# Audio_Input_Line_In.net
KiCad netlist of a schematic drawn in Altium Designer
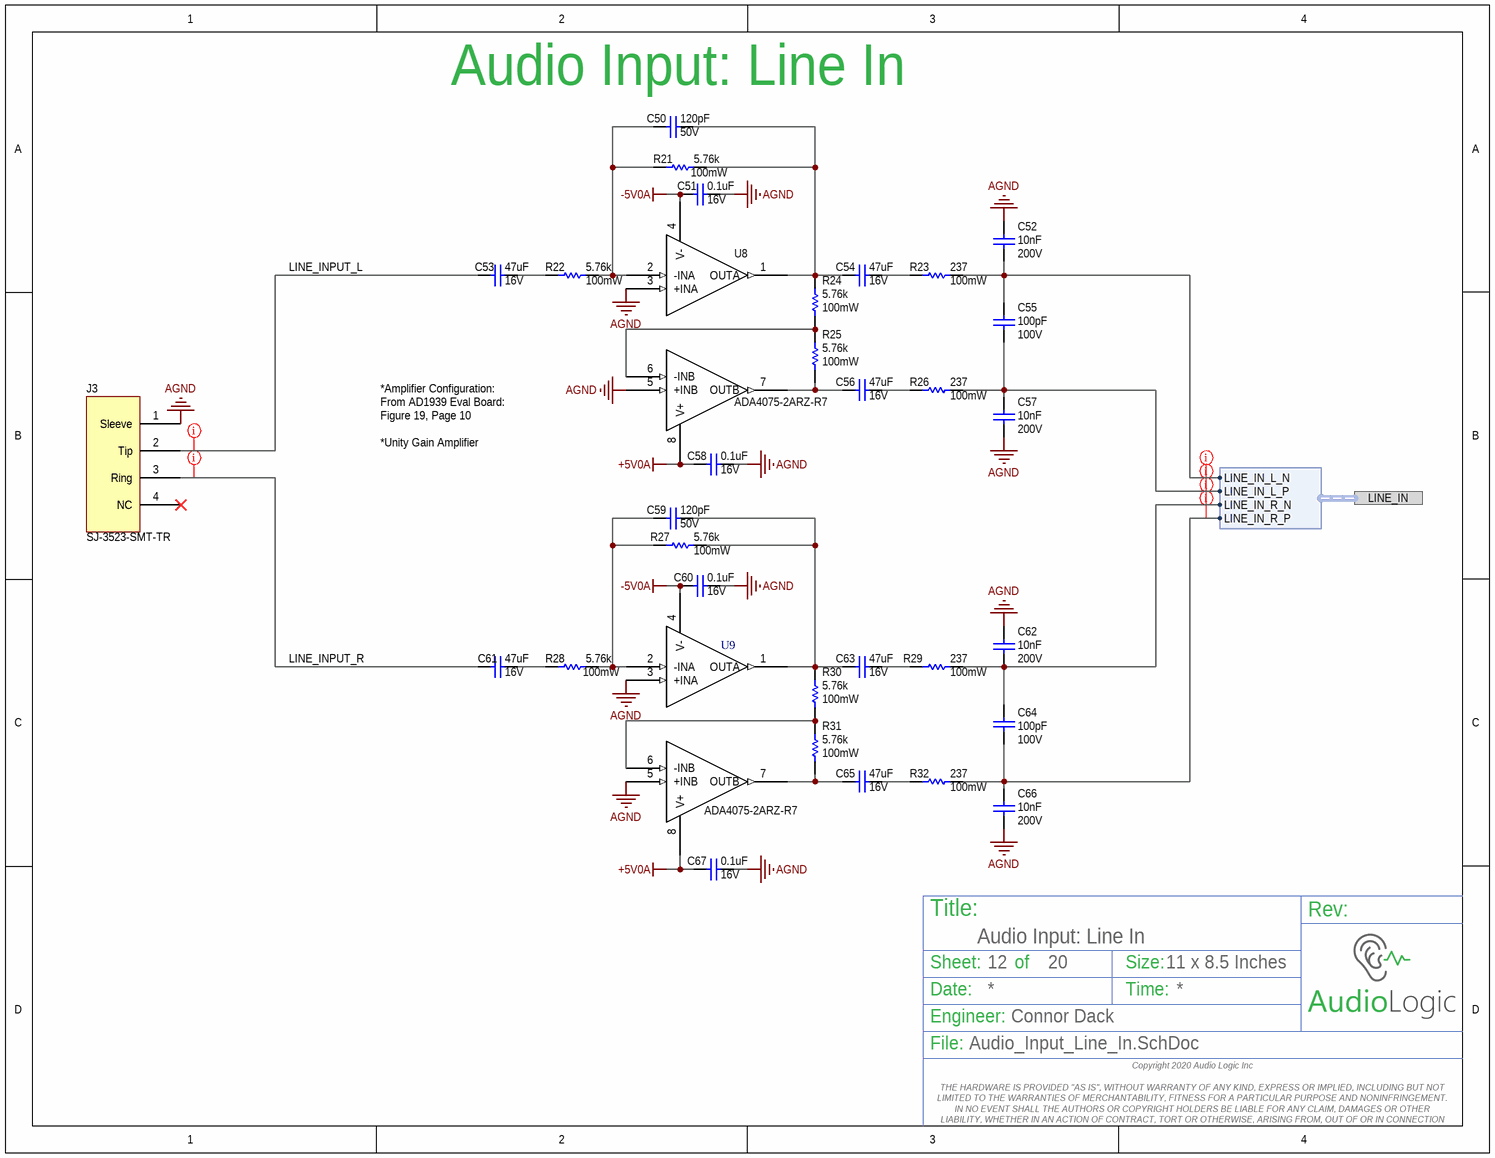
[diagram p0: Audio_Input_Line_In.SchDoc]

(export (version "E")
  (design (tool "Eeschema 10.0.6"))
  (components
    (comp (ref "C50")
      (value "CL10C121JB8NCNC")
      (footprint "3-0603_L")
      (description "120pF 50V Ceramic Capacitor C0G, NP0 0603 (1608 Metric) 0.063\" L x 0.031\" W (1.60mm x 0.80mm)")
      (fields
        (field (name "MANUFACTURER") "Samsung Electro-Mechanics America, Inc.")
        (field (name "TOLERANCE") "±5%")
        (field (name "VOLTAGE - RATED") "50V")
        (field (name "CAPACITANCE") "120pF")
      )
      (libsource (lib "Schematic_Components") (part "CL10C121JB8NCNC"))
    )
    (comp (ref "C51")
      (value "CL10F104ZO8NNNC")
      (footprint "3-0603_L")
      (description "CAP CER 0.1UF 16V Y5V 0603")
      (fields
        (field (name "MANUFACTURER") "Samsung")
        (field (name "TOLERANCE") "80%")
        (field (name "VOLTAGE RATING") "16V")
        (field (name "CAPACITANCE") "0.1uF")
      )
      (libsource (lib "Schematic_Components_CD") (part "CL10F104ZO8NNNC"))
    )
    (comp (ref "C52")
      (value "~")
      (footprint "3-0603_L")
      (description "CAP CER 10000PF 200V X7R 0603")
      (fields
        (field (name "MANUFACTURER") "KEMET")
        (field (name "MANUFACTURER PART NUMBER") "C0603C103J2RACTU")
        (field (name "VOLTAGE RATING") "200V")
        (field (name "CAPACITANCE") "10nF")
      )
      (libsource (lib "Miscellaneous Devices") (part "C0603C103J2RACTU"))
    )
    (comp (ref "C53")
      (value "CL32A476KOJNNNE")
      (footprint "C1210X25_L")
      (description "CAP CER 47UF 16V X5R 1210")
      (fields
        (field (name "MANUFACTURER") "Samsung")
        (field (name "TOLERANCE") "10%")
        (field (name "VOLTAGE RATING") "16V")
        (field (name "CAPACITANCE") "47uF")
      )
      (libsource (lib "Schematic_Components_CD") (part "CL32A476KOJNNNE"))
    )
    (comp (ref "C54")
      (value "CL32A476KOJNNNE")
      (footprint "C1210X25_L")
      (description "CAP CER 47UF 16V X5R 1210")
      (fields
        (field (name "MANUFACTURER") "Samsung")
        (field (name "TOLERANCE") "10%")
        (field (name "VOLTAGE RATING") "16V")
        (field (name "CAPACITANCE") "47uF")
      )
      (libsource (lib "Schematic_Components_CD") (part "CL32A476KOJNNNE"))
    )
    (comp (ref "C55")
      (value "C1608C0G2A101J")
      (footprint "3-0603_L")
      (description "CAP CER 100PF 100V 5% NP0 0603")
      (fields
        (field (name "MANUFACTURER") "TDK Corporation")
        (field (name "VOLTAGE - RATED") "100V")
        (field (name "TOLERANCE") "±5%")
        (field (name "CAPACITANCE") "100pF")
      )
      (libsource (lib "Schematic_Components") (part "C1608C0G2A101J"))
    )
    (comp (ref "C56")
      (value "CL32A476KOJNNNE")
      (footprint "C1210X25_L")
      (description "CAP CER 47UF 16V X5R 1210")
      (fields
        (field (name "MANUFACTURER") "Samsung")
        (field (name "TOLERANCE") "10%")
        (field (name "VOLTAGE RATING") "16V")
        (field (name "CAPACITANCE") "47uF")
      )
      (libsource (lib "Schematic_Components_CD") (part "CL32A476KOJNNNE"))
    )
    (comp (ref "C57")
      (value "~")
      (footprint "3-0603_L")
      (description "CAP CER 10000PF 200V X7R 0603")
      (fields
        (field (name "MANUFACTURER") "KEMET")
        (field (name "MANUFACTURER PART NUMBER") "C0603C103J2RACTU")
        (field (name "VOLTAGE RATING") "200V")
        (field (name "CAPACITANCE") "10nF")
      )
      (libsource (lib "Miscellaneous Devices") (part "C0603C103J2RACTU"))
    )
    (comp (ref "C58")
      (value "CL10F104ZO8NNNC")
      (footprint "3-0603_L")
      (description "CAP CER 0.1UF 16V Y5V 0603")
      (fields
        (field (name "MANUFACTURER") "Samsung")
        (field (name "TOLERANCE") "80%")
        (field (name "VOLTAGE RATING") "16V")
        (field (name "CAPACITANCE") "0.1uF")
      )
      (libsource (lib "Schematic_Components_CD") (part "CL10F104ZO8NNNC"))
    )
    (comp (ref "C59")
      (value "CL10C121JB8NCNC")
      (footprint "3-0603_L")
      (description "120pF 50V Ceramic Capacitor C0G, NP0 0603 (1608 Metric) 0.063\" L x 0.031\" W (1.60mm x 0.80mm)")
      (fields
        (field (name "MANUFACTURER") "Samsung Electro-Mechanics America, Inc.")
        (field (name "TOLERANCE") "±5%")
        (field (name "VOLTAGE - RATED") "50V")
        (field (name "CAPACITANCE") "120pF")
      )
      (libsource (lib "Schematic_Components") (part "CL10C121JB8NCNC"))
    )
    (comp (ref "C60")
      (value "CL10F104ZO8NNNC")
      (footprint "3-0603_L")
      (description "CAP CER 0.1UF 16V Y5V 0603")
      (fields
        (field (name "MANUFACTURER") "Samsung")
        (field (name "TOLERANCE") "80%")
        (field (name "VOLTAGE RATING") "16V")
        (field (name "CAPACITANCE") "0.1uF")
      )
      (libsource (lib "Schematic_Components_CD") (part "CL10F104ZO8NNNC"))
    )
    (comp (ref "C61")
      (value "CL32A476KOJNNNE")
      (footprint "C1210X25_L")
      (description "CAP CER 47UF 16V X5R 1210")
      (fields
        (field (name "MANUFACTURER") "Samsung")
        (field (name "TOLERANCE") "10%")
        (field (name "VOLTAGE RATING") "16V")
        (field (name "CAPACITANCE") "47uF")
      )
      (libsource (lib "Schematic_Components_CD") (part "CL32A476KOJNNNE"))
    )
    (comp (ref "C62")
      (value "~")
      (footprint "3-0603_L")
      (description "CAP CER 10000PF 200V X7R 0603")
      (fields
        (field (name "MANUFACTURER") "KEMET")
        (field (name "MANUFACTURER PART NUMBER") "C0603C103J2RACTU")
        (field (name "VOLTAGE RATING") "200V")
        (field (name "CAPACITANCE") "10nF")
      )
      (libsource (lib "Miscellaneous Devices") (part "C0603C103J2RACTU"))
    )
    (comp (ref "C63")
      (value "CL32A476KOJNNNE")
      (footprint "C1210X25_L")
      (description "CAP CER 47UF 16V X5R 1210")
      (fields
        (field (name "MANUFACTURER") "Samsung")
        (field (name "TOLERANCE") "10%")
        (field (name "VOLTAGE RATING") "16V")
        (field (name "CAPACITANCE") "47uF")
      )
      (libsource (lib "Schematic_Components_CD") (part "CL32A476KOJNNNE"))
    )
    (comp (ref "C64")
      (value "C1608C0G2A101J")
      (footprint "3-0603_L")
      (description "CAP CER 100PF 100V 5% NP0 0603")
      (fields
        (field (name "MANUFACTURER") "TDK Corporation")
        (field (name "VOLTAGE - RATED") "100V")
        (field (name "TOLERANCE") "±5%")
        (field (name "CAPACITANCE") "100pF")
      )
      (libsource (lib "Schematic_Components") (part "C1608C0G2A101J"))
    )
    (comp (ref "C65")
      (value "CL32A476KOJNNNE")
      (footprint "C1210X25_L")
      (description "CAP CER 47UF 16V X5R 1210")
      (fields
        (field (name "MANUFACTURER") "Samsung")
        (field (name "TOLERANCE") "10%")
        (field (name "VOLTAGE RATING") "16V")
        (field (name "CAPACITANCE") "47uF")
      )
      (libsource (lib "Schematic_Components_CD") (part "CL32A476KOJNNNE"))
    )
    (comp (ref "C66")
      (value "~")
      (footprint "3-0603_L")
      (description "CAP CER 10000PF 200V X7R 0603")
      (fields
        (field (name "MANUFACTURER") "KEMET")
        (field (name "MANUFACTURER PART NUMBER") "C0603C103J2RACTU")
        (field (name "VOLTAGE RATING") "200V")
        (field (name "CAPACITANCE") "10nF")
      )
      (libsource (lib "Miscellaneous Devices") (part "C0603C103J2RACTU"))
    )
    (comp (ref "C67")
      (value "CL10F104ZO8NNNC")
      (footprint "3-0603_L")
      (description "CAP CER 0.1UF 16V Y5V 0603")
      (fields
        (field (name "MANUFACTURER") "Samsung")
        (field (name "TOLERANCE") "80%")
        (field (name "VOLTAGE RATING") "16V")
        (field (name "CAPACITANCE") "0.1uF")
      )
      (libsource (lib "Schematic_Components_CD") (part "CL10F104ZO8NNNC"))
    )
    (comp (ref "J3")
      (value "SJ-3523-SMT-TR")
      (footprint "SJ-3523-SMT-TR")
      (description "3.50mm (0.141\", 1/8\", Mini Plug) - Headphone Phone Jack Stereo Connector Solder")
      (fields
        (field (name "MANUFACTURER") "CUI Inc.")
        (field (name "MANUFACTURER PART NUMBER") "SJ-3523-SMT-TR")
        (field (name "PUBLISHER") "Altium Limited")
      )
      (libsource (lib "NIH_DE0_Nano_Daughter_Card_Library") (part "SJ-3523-SMT-TR"))
    )
    (comp (ref "R21")
      (value "ERJ-3EKF5761V")
      (footprint "3-0603_R_L")
      (description "RES SMD 5.76K OHM 1% 1/10W 0603")
      (fields
        (field (name "MANUFACTURER") "Panasonic Electronic Components")
        (field (name "TOLERANCE") "±1%")
        (field (name "POWER (WATTS)") "100mW")
        (field (name "RESISTANCE (OHMS)") "5.76k")
      )
      (libsource (lib "Schematic_Components") (part "ERJ-3EKF5761V"))
    )
    (comp (ref "R22")
      (value "ERJ-3EKF5761V")
      (footprint "3-0603_R_L")
      (description "RES SMD 5.76K OHM 1% 1/10W 0603")
      (fields
        (field (name "MANUFACTURER") "Panasonic Electronic Components")
        (field (name "TOLERANCE") "±1%")
        (field (name "POWER (WATTS)") "100mW")
        (field (name "RESISTANCE (OHMS)") "5.76k")
      )
      (libsource (lib "Schematic_Components") (part "ERJ-3EKF5761V"))
    )
    (comp (ref "R23")
      (value "ERJ-3EKF2370V")
      (footprint "3-0603_R_L")
      (description "RES SMD 237 OHM 1% 1/10W 0603")
      (fields
        (field (name "MANUFACTURER") "Panasonic Electronic Components")
        (field (name "TOLERANCE") "±1%")
        (field (name "POWER (WATTS)") "100mW")
        (field (name "RESISTANCE (OHMS)") "237")
      )
      (libsource (lib "Schematic_Components") (part "ERJ-3EKF2370V"))
    )
    (comp (ref "R24")
      (value "ERJ-3EKF5761V")
      (footprint "3-0603_R_L")
      (description "RES SMD 5.76K OHM 1% 1/10W 0603")
      (fields
        (field (name "MANUFACTURER") "Panasonic Electronic Components")
        (field (name "TOLERANCE") "±1%")
        (field (name "POWER (WATTS)") "100mW")
        (field (name "RESISTANCE (OHMS)") "5.76k")
      )
      (libsource (lib "Schematic_Components") (part "ERJ-3EKF5761V"))
    )
    (comp (ref "R25")
      (value "ERJ-3EKF5761V")
      (footprint "3-0603_R_L")
      (description "RES SMD 5.76K OHM 1% 1/10W 0603")
      (fields
        (field (name "MANUFACTURER") "Panasonic Electronic Components")
        (field (name "TOLERANCE") "±1%")
        (field (name "POWER (WATTS)") "100mW")
        (field (name "RESISTANCE (OHMS)") "5.76k")
      )
      (libsource (lib "Schematic_Components") (part "ERJ-3EKF5761V"))
    )
    (comp (ref "R26")
      (value "ERJ-3EKF2370V")
      (footprint "3-0603_R_L")
      (description "RES SMD 237 OHM 1% 1/10W 0603")
      (fields
        (field (name "MANUFACTURER") "Panasonic Electronic Components")
        (field (name "TOLERANCE") "±1%")
        (field (name "POWER (WATTS)") "100mW")
        (field (name "RESISTANCE (OHMS)") "237")
      )
      (libsource (lib "Schematic_Components") (part "ERJ-3EKF2370V"))
    )
    (comp (ref "R27")
      (value "ERJ-3EKF5761V")
      (footprint "3-0603_R_L")
      (description "RES SMD 5.76K OHM 1% 1/10W 0603")
      (fields
        (field (name "MANUFACTURER") "Panasonic Electronic Components")
        (field (name "TOLERANCE") "±1%")
        (field (name "POWER (WATTS)") "100mW")
        (field (name "RESISTANCE (OHMS)") "5.76k")
      )
      (libsource (lib "Schematic_Components") (part "ERJ-3EKF5761V"))
    )
    (comp (ref "R28")
      (value "ERJ-3EKF5761V")
      (footprint "3-0603_R_L")
      (description "RES SMD 5.76K OHM 1% 1/10W 0603")
      (fields
        (field (name "MANUFACTURER") "Panasonic Electronic Components")
        (field (name "TOLERANCE") "±1%")
        (field (name "POWER (WATTS)") "100mW")
        (field (name "RESISTANCE (OHMS)") "5.76k")
      )
      (libsource (lib "Schematic_Components") (part "ERJ-3EKF5761V"))
    )
    (comp (ref "R29")
      (value "ERJ-3EKF2370V")
      (footprint "3-0603_R_L")
      (description "RES SMD 237 OHM 1% 1/10W 0603")
      (fields
        (field (name "MANUFACTURER") "Panasonic Electronic Components")
        (field (name "TOLERANCE") "±1%")
        (field (name "POWER (WATTS)") "100mW")
        (field (name "RESISTANCE (OHMS)") "237")
      )
      (libsource (lib "Schematic_Components") (part "ERJ-3EKF2370V"))
    )
    (comp (ref "R30")
      (value "ERJ-3EKF5761V")
      (footprint "3-0603_R_L")
      (description "RES SMD 5.76K OHM 1% 1/10W 0603")
      (fields
        (field (name "MANUFACTURER") "Panasonic Electronic Components")
        (field (name "TOLERANCE") "±1%")
        (field (name "POWER (WATTS)") "100mW")
        (field (name "RESISTANCE (OHMS)") "5.76k")
      )
      (libsource (lib "Schematic_Components") (part "ERJ-3EKF5761V"))
    )
    (comp (ref "R31")
      (value "ERJ-3EKF5761V")
      (footprint "3-0603_R_L")
      (description "RES SMD 5.76K OHM 1% 1/10W 0603")
      (fields
        (field (name "MANUFACTURER") "Panasonic Electronic Components")
        (field (name "TOLERANCE") "±1%")
        (field (name "POWER (WATTS)") "100mW")
        (field (name "RESISTANCE (OHMS)") "5.76k")
      )
      (libsource (lib "Schematic_Components") (part "ERJ-3EKF5761V"))
    )
    (comp (ref "R32")
      (value "ERJ-3EKF2370V")
      (footprint "3-0603_R_L")
      (description "RES SMD 237 OHM 1% 1/10W 0603")
      (fields
        (field (name "MANUFACTURER") "Panasonic Electronic Components")
        (field (name "TOLERANCE") "±1%")
        (field (name "POWER (WATTS)") "100mW")
        (field (name "RESISTANCE (OHMS)") "237")
      )
      (libsource (lib "Schematic_Components") (part "ERJ-3EKF2370V"))
    )
    (comp (ref "U8")
      (value "ADA4075-2ARZ-R7")
      (footprint "SOIC127P600X175-8L")
      (description "IC OPAMP GP 6.5MHZ 8SOIC")
      (fields
        (field (name "MANUFACTURER") "Analog Devices Inc.")
        (field (name "MANUFACTURER PART NUMBER") "ADA4075-2ARZ-R7")
      )
      (libsource (lib "Schematic_Components_CD") (part "ADA4075-2ARZ-R7"))
    )
    (comp (ref "U9")
      (value "ADA4075-2ARZ-R7")
      (footprint "SOIC127P600X175-8L")
      (description "IC OPAMP GP 6.5MHZ 8SOIC")
      (fields
        (field (name "MANUFACTURER") "Analog Devices Inc.")
        (field (name "MANUFACTURER PART NUMBER") "ADA4075-2ARZ-R7")
      )
      (libsource (lib "Schematic_Components_CD") (part "ADA4075-2ARZ-R7"))
    )
  )
  (nets
    (net (code "2") (name "+5V0A") (class "Default")
      (node (ref "C58") (pin "2") (pinfunction "2_2") (pintype "passive"))
      (node (ref "C67") (pin "2") (pinfunction "2_2") (pintype "passive"))
      (node (ref "U8") (pin "8") (pinfunction "V+_8") (pintype "passive"))
      (node (ref "U9") (pin "8") (pinfunction "V+_8") (pintype "passive"))
    )
    (net (code "3") (name "-5V0A") (class "Default")
      (node (ref "C51") (pin "2") (pinfunction "2_2") (pintype "passive"))
      (node (ref "C60") (pin "2") (pinfunction "2_2") (pintype "passive"))
      (node (ref "U8") (pin "4") (pinfunction "V-_4") (pintype "passive"))
      (node (ref "U9") (pin "4") (pinfunction "V-_4") (pintype "passive"))
    )
    (net (code "4") (name "/LINE_INPUT_L") (class "Default")
      (node (ref "C53") (pin "1") (pinfunction "1_1") (pintype "passive"))
      (node (ref "J3") (pin "2") (pinfunction "Tip_2") (pintype "passive"))
    )
    (net (code "5") (name "/LINE_INPUT_R") (class "Default")
      (node (ref "C61") (pin "1") (pinfunction "1_1") (pintype "passive"))
      (node (ref "J3") (pin "3") (pinfunction "Ring_3") (pintype "passive"))
    )
    (net (code "7") (name "AGND") (class "Default")
      (node (ref "C51") (pin "1") (pinfunction "1_1") (pintype "passive"))
      (node (ref "C52") (pin "2") (pinfunction "2_2") (pintype "passive"))
      (node (ref "C57") (pin "1") (pinfunction "1_1") (pintype "passive"))
      (node (ref "C58") (pin "1") (pinfunction "1_1") (pintype "passive"))
      (node (ref "C60") (pin "1") (pinfunction "1_1") (pintype "passive"))
      (node (ref "C62") (pin "2") (pinfunction "2_2") (pintype "passive"))
      (node (ref "C66") (pin "1") (pinfunction "1_1") (pintype "passive"))
      (node (ref "C67") (pin "1") (pinfunction "1_1") (pintype "passive"))
      (node (ref "J3") (pin "1") (pinfunction "Sleeve_1") (pintype "passive"))
      (node (ref "U8") (pin "3") (pinfunction "+INA_3") (pintype "input"))
      (node (ref "U8") (pin "5") (pinfunction "+INB_5") (pintype "input"))
      (node (ref "U9") (pin "3") (pinfunction "+INA_3") (pintype "input"))
      (node (ref "U9") (pin "5") (pinfunction "+INB_5") (pintype "input"))
    )
    (net (code "8") (name "Net-(C52-Pad1)") (class "Default")
      (node (ref "C52") (pin "1") (pinfunction "1_1") (pintype "passive"))
      (node (ref "C55") (pin "2") (pinfunction "2_2") (pintype "passive"))
      (node (ref "R23") (pin "2") (pinfunction "2_2") (pintype "passive"))
    )
    (net (code "9") (name "Net-(C53-Pad2)") (class "Default")
      (node (ref "C53") (pin "2") (pinfunction "2_2") (pintype "passive"))
      (node (ref "R22") (pin "1") (pinfunction "1_1") (pintype "passive"))
    )
    (net (code "10") (name "Net-(C54-Pad2)") (class "Default")
      (node (ref "C54") (pin "2") (pinfunction "2_2") (pintype "passive"))
      (node (ref "R23") (pin "1") (pinfunction "1_1") (pintype "passive"))
    )
    (net (code "11") (name "Net-(C55-Pad1)") (class "Default")
      (node (ref "C55") (pin "1") (pinfunction "1_1") (pintype "passive"))
      (node (ref "C57") (pin "2") (pinfunction "2_2") (pintype "passive"))
      (node (ref "R26") (pin "2") (pinfunction "2_2") (pintype "passive"))
    )
    (net (code "12") (name "Net-(C56-Pad2)") (class "Default")
      (node (ref "C56") (pin "2") (pinfunction "2_2") (pintype "passive"))
      (node (ref "R26") (pin "1") (pinfunction "1_1") (pintype "passive"))
    )
    (net (code "13") (name "Net-(C61-Pad2)") (class "Default")
      (node (ref "C61") (pin "2") (pinfunction "2_2") (pintype "passive"))
      (node (ref "R28") (pin "1") (pinfunction "1_1") (pintype "passive"))
    )
    (net (code "14") (name "Net-(C62-Pad1)") (class "Default")
      (node (ref "C62") (pin "1") (pinfunction "1_1") (pintype "passive"))
      (node (ref "C64") (pin "2") (pinfunction "2_2") (pintype "passive"))
      (node (ref "R29") (pin "2") (pinfunction "2_2") (pintype "passive"))
    )
    (net (code "15") (name "Net-(C63-Pad2)") (class "Default")
      (node (ref "C63") (pin "2") (pinfunction "2_2") (pintype "passive"))
      (node (ref "R29") (pin "1") (pinfunction "1_1") (pintype "passive"))
    )
    (net (code "16") (name "Net-(C64-Pad1)") (class "Default")
      (node (ref "C64") (pin "1") (pinfunction "1_1") (pintype "passive"))
      (node (ref "C66") (pin "2") (pinfunction "2_2") (pintype "passive"))
      (node (ref "R32") (pin "2") (pinfunction "2_2") (pintype "passive"))
    )
    (net (code "17") (name "Net-(C65-Pad2)") (class "Default")
      (node (ref "C65") (pin "2") (pinfunction "2_2") (pintype "passive"))
      (node (ref "R32") (pin "1") (pinfunction "1_1") (pintype "passive"))
    )
    (net (code "18") (name "Net-(U8--INA)") (class "Default")
      (node (ref "C50") (pin "1") (pinfunction "1_1") (pintype "passive"))
      (node (ref "R21") (pin "1") (pinfunction "1_1") (pintype "passive"))
      (node (ref "R22") (pin "2") (pinfunction "2_2") (pintype "passive"))
      (node (ref "U8") (pin "2") (pinfunction "-INA_2") (pintype "input"))
    )
    (net (code "19") (name "Net-(U8--INB)") (class "Default")
      (node (ref "R24") (pin "2") (pinfunction "2_2") (pintype "passive"))
      (node (ref "R25") (pin "2") (pinfunction "2_2") (pintype "passive"))
      (node (ref "U8") (pin "6") (pinfunction "-INB_6") (pintype "input"))
    )
    (net (code "20") (name "Net-(U8-OUTA)") (class "Default")
      (node (ref "C50") (pin "2") (pinfunction "2_2") (pintype "passive"))
      (node (ref "C54") (pin "1") (pinfunction "1_1") (pintype "passive"))
      (node (ref "R21") (pin "2") (pinfunction "2_2") (pintype "passive"))
      (node (ref "R24") (pin "1") (pinfunction "1_1") (pintype "passive"))
      (node (ref "U8") (pin "1") (pinfunction "OUTA_1") (pintype "output"))
    )
    (net (code "21") (name "Net-(U8-OUTB)") (class "Default")
      (node (ref "C56") (pin "1") (pinfunction "1_1") (pintype "passive"))
      (node (ref "R25") (pin "1") (pinfunction "1_1") (pintype "passive"))
      (node (ref "U8") (pin "7") (pinfunction "OUTB_7") (pintype "output"))
    )
    (net (code "22") (name "Net-(U9--INA)") (class "Default")
      (node (ref "C59") (pin "1") (pinfunction "1_1") (pintype "passive"))
      (node (ref "R27") (pin "1") (pinfunction "1_1") (pintype "passive"))
      (node (ref "R28") (pin "2") (pinfunction "2_2") (pintype "passive"))
      (node (ref "U9") (pin "2") (pinfunction "-INA_2") (pintype "input"))
    )
    (net (code "23") (name "Net-(U9--INB)") (class "Default")
      (node (ref "R30") (pin "1") (pinfunction "1_1") (pintype "passive"))
      (node (ref "R31") (pin "2") (pinfunction "2_2") (pintype "passive"))
      (node (ref "U9") (pin "6") (pinfunction "-INB_6") (pintype "input"))
    )
    (net (code "24") (name "Net-(U9-OUTA)") (class "Default")
      (node (ref "C59") (pin "2") (pinfunction "2_2") (pintype "passive"))
      (node (ref "C63") (pin "1") (pinfunction "1_1") (pintype "passive"))
      (node (ref "R27") (pin "2") (pinfunction "2_2") (pintype "passive"))
      (node (ref "R30") (pin "2") (pinfunction "2_2") (pintype "passive"))
      (node (ref "U9") (pin "1") (pinfunction "OUTA_1") (pintype "output"))
    )
    (net (code "25") (name "Net-(U9-OUTB)") (class "Default")
      (node (ref "C65") (pin "1") (pinfunction "1_1") (pintype "passive"))
      (node (ref "R31") (pin "1") (pinfunction "1_1") (pintype "passive"))
      (node (ref "U9") (pin "7") (pinfunction "OUTB_7") (pintype "output"))
    )
    (net (code "26") (name "unconnected-(J3-NC-Pad4)") (class "Default")
      (node (ref "J3") (pin "4") (pinfunction "NC_4") (pintype "passive+no_connect"))
    )
  )
)
